# main.net
KiCad netlist of a schematic drawn in EAGLE
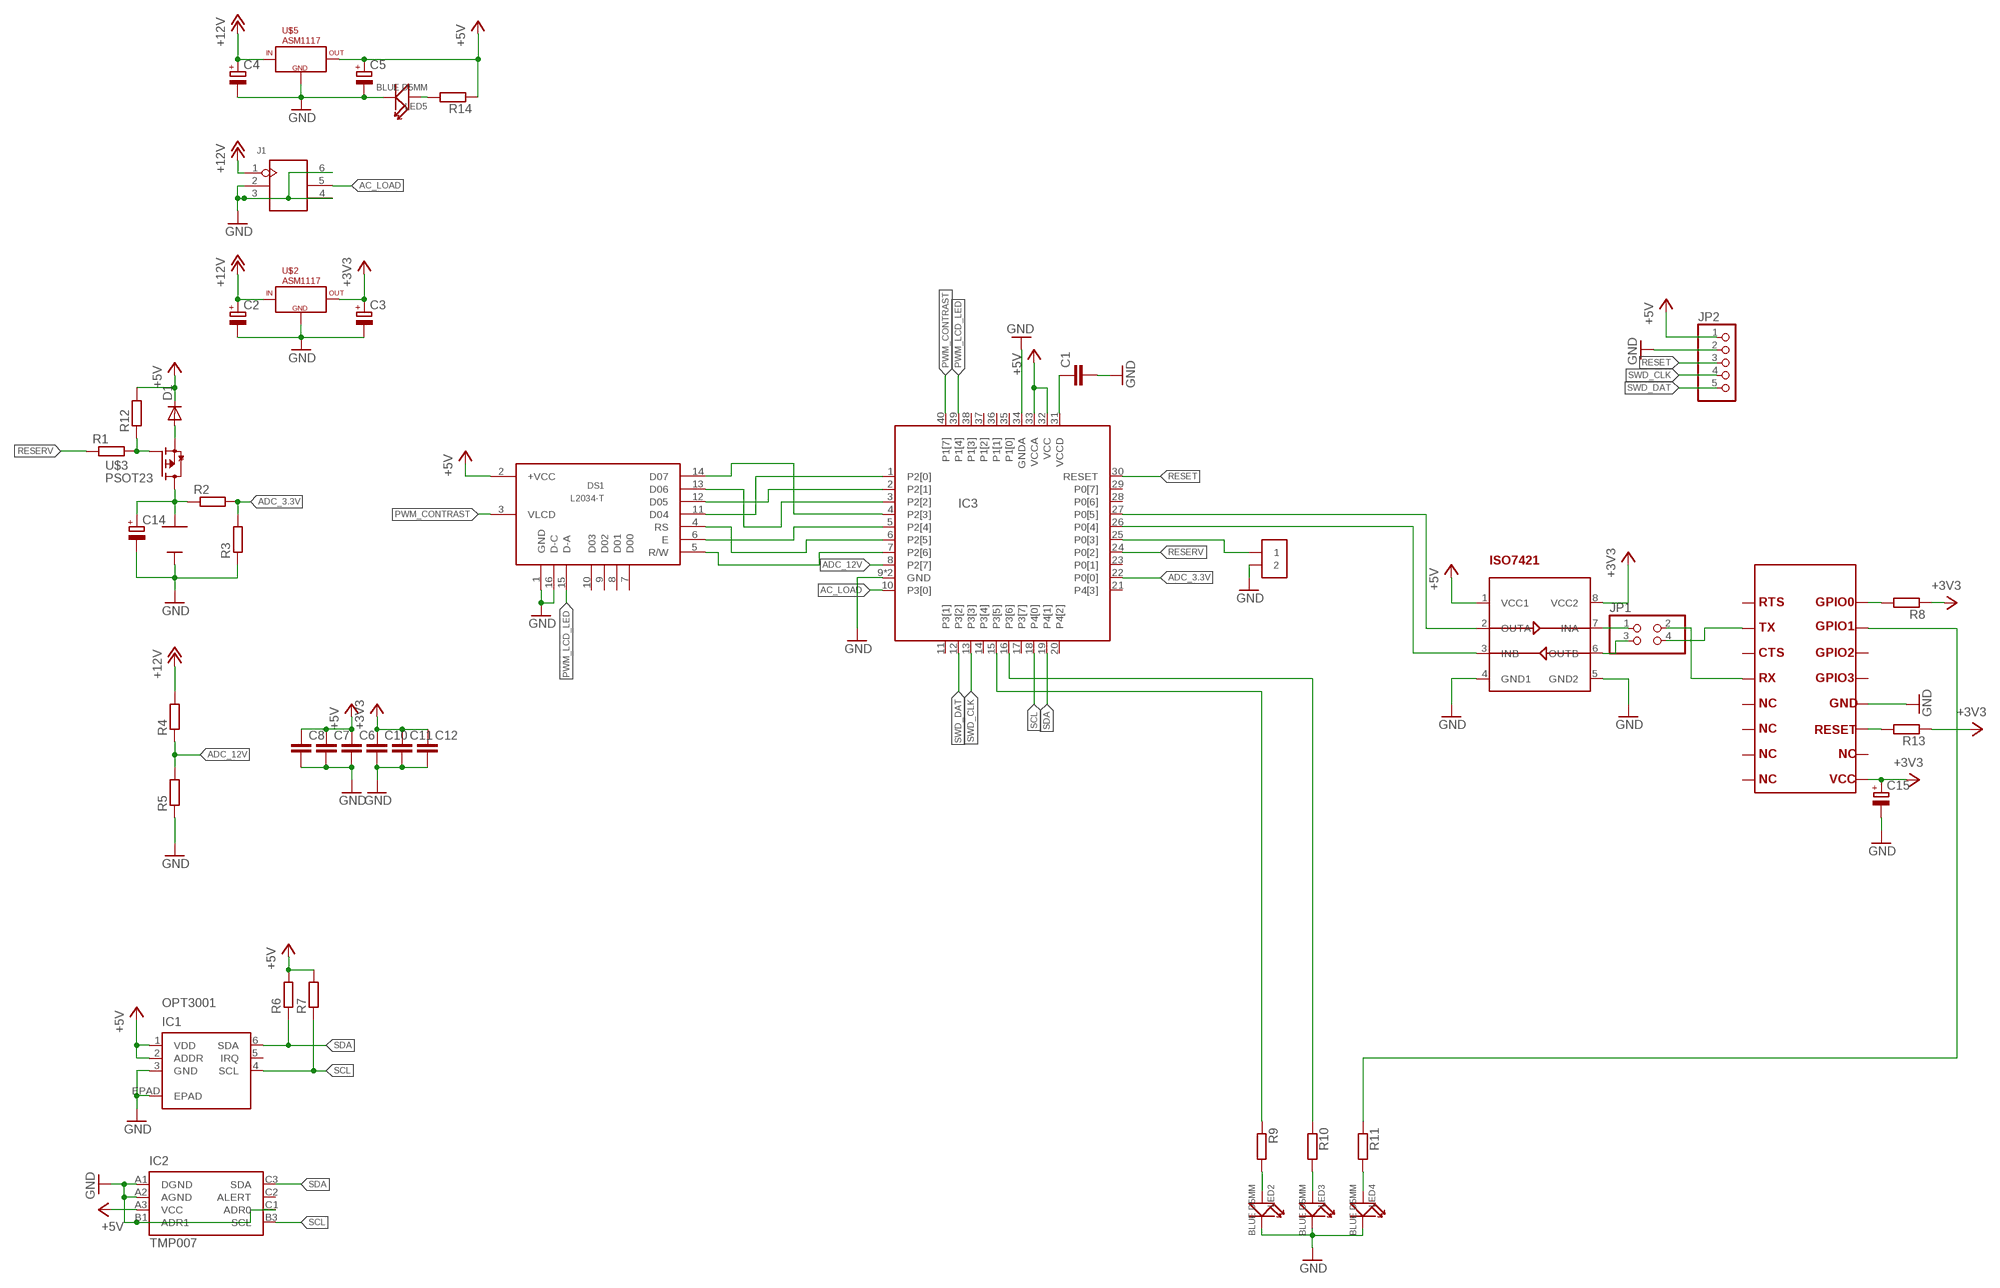
[diagram p0: schematic, sheet 1]

(export (version "E")
  (design (tool "Eeschema 10.0.6"))
  (components
    (comp (ref "BAT1")
      (value "CR2032_DIP")
      (footprint "eagle-import:CR2032_DIP")
      (libsource (lib "eagle-import") (part "CR2032_DIP"))
    )
    (comp (ref "C1")
      (value "C-EUC0805")
      (footprint "eagle-import:C0805")
      (libsource (lib "eagle-import") (part "C-EUC0805"))
    )
    (comp (ref "C2")
      (value "CPOL-EU150CLZ-0810")
      (footprint "eagle-import:150CLZ-0810")
      (libsource (lib "eagle-import") (part "CPOL-EU150CLZ-0810"))
    )
    (comp (ref "C3")
      (value "CPOL-EU150CLZ-0810")
      (footprint "eagle-import:150CLZ-0810")
      (libsource (lib "eagle-import") (part "CPOL-EU150CLZ-0810"))
    )
    (comp (ref "C4")
      (value "CPOL-EU150CLZ-0810")
      (footprint "eagle-import:150CLZ-0810")
      (libsource (lib "eagle-import") (part "CPOL-EU150CLZ-0810"))
    )
    (comp (ref "C5")
      (value "CPOL-EU150CLZ-0810")
      (footprint "eagle-import:150CLZ-0810")
      (libsource (lib "eagle-import") (part "CPOL-EU150CLZ-0810"))
    )
    (comp (ref "C6")
      (value "C-EUC0805")
      (footprint "eagle-import:C0805")
      (libsource (lib "eagle-import") (part "C-EUC0805"))
    )
    (comp (ref "C7")
      (value "C-EUC0805")
      (footprint "eagle-import:C0805")
      (libsource (lib "eagle-import") (part "C-EUC0805"))
    )
    (comp (ref "C8")
      (value "C-EUC0805")
      (footprint "eagle-import:C0805")
      (libsource (lib "eagle-import") (part "C-EUC0805"))
    )
    (comp (ref "C10")
      (value "C-EUC0805")
      (footprint "eagle-import:C0805")
      (libsource (lib "eagle-import") (part "C-EUC0805"))
    )
    (comp (ref "C11")
      (value "C-EUC0805")
      (footprint "eagle-import:C0805")
      (libsource (lib "eagle-import") (part "C-EUC0805"))
    )
    (comp (ref "C12")
      (value "C-EUC0805")
      (footprint "eagle-import:C0805")
      (libsource (lib "eagle-import") (part "C-EUC0805"))
    )
    (comp (ref "C14")
      (value "CPOL-EUSMCD")
      (footprint "eagle-import:SMC_D")
      (libsource (lib "eagle-import") (part "CPOL-EUSMCD"))
    )
    (comp (ref "C15")
      (value "CPOL-EUSMCA")
      (footprint "eagle-import:SMC_A")
      (libsource (lib "eagle-import") (part "CPOL-EUSMCA"))
    )
    (comp (ref "D1")
      (value "DIODE-DO-214AC")
      (footprint "eagle-import:DO-214AC")
      (libsource (lib "eagle-import") (part "DIODE-DO-214AC"))
    )
    (comp (ref "DS1")
      (value "L2034-T")
      (footprint "eagle-import:L2034-T")
      (libsource (lib "eagle-import") (part "L2034-T"))
    )
    (comp (ref "IC1")
      (value "OPT3001")
      (footprint "eagle-import:USON6")
      (libsource (lib "eagle-import") (part "OPT3001"))
    )
    (comp (ref "IC2")
      (value "TMP007")
      (footprint "eagle-import:XBGA8")
      (libsource (lib "eagle-import") (part "TMP007"))
    )
    (comp (ref "IC3")
      (value "CY8C4245-LQI-LONG")
      (footprint "eagle-import:QFN40-LONG")
      (libsource (lib "eagle-import") (part "CY8C4245-LQI-LONG"))
    )
    (comp (ref "J1")
      (value "DIP-BLUE-MALE-HEADER-VERT(2X3P-2.54)")
      (footprint "eagle-import:H2X3-2.54")
      (fields (field (name "MPN") "P125-1203A0BS116A1"))
      (libsource (lib "eagle-import") (part "DIP-BLUE-MALE-HEADER-VERT(2X3P-2.54)"))
    )
    (comp (ref "JP1")
      (value "PINHD-2X2")
      (footprint "eagle-import:2X02")
      (libsource (lib "eagle-import") (part "PINHD-2X2"))
    )
    (comp (ref "JP2")
      (value "PINHD-1X5")
      (footprint "eagle-import:1X05")
      (libsource (lib "eagle-import") (part "PINHD-1X5"))
    )
    (comp (ref "LED2")
      (value "BLUE D5MM")
      (footprint "eagle-import:LED2-2.54-D5.0MM")
      (fields (field (name "MPN") "BH504DC"))
      (libsource (lib "eagle-import") (part "DIP-LED-BLUE-BLUE-5MM(2P-D5MM)"))
    )
    (comp (ref "LED3")
      (value "BLUE D5MM")
      (footprint "eagle-import:LED2-2.54-D5.0MM")
      (fields (field (name "MPN") "BH504DC"))
      (libsource (lib "eagle-import") (part "DIP-LED-BLUE-BLUE-5MM(2P-D5MM)"))
    )
    (comp (ref "LED4")
      (value "BLUE D5MM")
      (footprint "eagle-import:LED2-2.54-D5.0MM")
      (fields (field (name "MPN") "BH504DC"))
      (libsource (lib "eagle-import") (part "DIP-LED-BLUE-BLUE-5MM(2P-D5MM)"))
    )
    (comp (ref "LED5")
      (value "BLUE D5MM")
      (footprint "eagle-import:LED2-2.54-D5.0MM")
      (fields (field (name "MPN") "BH504DC"))
      (libsource (lib "eagle-import") (part "DIP-LED-BLUE-BLUE-5MM(2P-D5MM)"))
    )
    (comp (ref "R1")
      (value "R-EU_M0805")
      (footprint "eagle-import:M0805")
      (libsource (lib "eagle-import") (part "R-EU_M0805"))
    )
    (comp (ref "R2")
      (value "R-EU_M0805")
      (footprint "eagle-import:M0805")
      (libsource (lib "eagle-import") (part "R-EU_M0805"))
    )
    (comp (ref "R3")
      (value "R-EU_M0805")
      (footprint "eagle-import:M0805")
      (libsource (lib "eagle-import") (part "R-EU_M0805"))
    )
    (comp (ref "R4")
      (value "R-EU_M0805")
      (footprint "eagle-import:M0805")
      (libsource (lib "eagle-import") (part "R-EU_M0805"))
    )
    (comp (ref "R5")
      (value "R-EU_M0805")
      (footprint "eagle-import:M0805")
      (libsource (lib "eagle-import") (part "R-EU_M0805"))
    )
    (comp (ref "R6")
      (value "R-EU_M0805")
      (footprint "eagle-import:M0805")
      (libsource (lib "eagle-import") (part "R-EU_M0805"))
    )
    (comp (ref "R7")
      (value "R-EU_M0805")
      (footprint "eagle-import:M0805")
      (libsource (lib "eagle-import") (part "R-EU_M0805"))
    )
    (comp (ref "R8")
      (value "R-EU_M0805")
      (footprint "eagle-import:M0805")
      (libsource (lib "eagle-import") (part "R-EU_M0805"))
    )
    (comp (ref "R9")
      (value "R-EU_M0805")
      (footprint "eagle-import:M0805")
      (libsource (lib "eagle-import") (part "R-EU_M0805"))
    )
    (comp (ref "R10")
      (value "R-EU_M0805")
      (footprint "eagle-import:M0805")
      (libsource (lib "eagle-import") (part "R-EU_M0805"))
    )
    (comp (ref "R11")
      (value "R-EU_M0805")
      (footprint "eagle-import:M0805")
      (libsource (lib "eagle-import") (part "R-EU_M0805"))
    )
    (comp (ref "R12")
      (value "R-EU_M0805")
      (footprint "eagle-import:M0805")
      (libsource (lib "eagle-import") (part "R-EU_M0805"))
    )
    (comp (ref "R13")
      (value "R-EU_M0805")
      (footprint "eagle-import:M0805")
      (libsource (lib "eagle-import") (part "R-EU_M0805"))
    )
    (comp (ref "R14")
      (value "R-EU_M0805")
      (footprint "eagle-import:M0805")
      (libsource (lib "eagle-import") (part "R-EU_M0805"))
    )
    (comp (ref "U$1")
      (value "HM-11")
      (footprint "eagle-import:HM-11")
      (libsource (lib "eagle-import") (part "HM-11"))
    )
    (comp (ref "U$2")
      (value "ASM1117")
      (footprint "eagle-import:SOT223")
      (libsource (lib "eagle-import") (part "ASM1117"))
    )
    (comp (ref "U$3")
      (value "PSOT23")
      (footprint "eagle-import:SOT23")
      (libsource (lib "eagle-import") (part "PSOT23"))
    )
    (comp (ref "U$5")
      (value "ASM1117")
      (footprint "eagle-import:SOT223")
      (libsource (lib "eagle-import") (part "ASM1117"))
    )
    (comp (ref "U$6")
      (value "ISO7421")
      (footprint "eagle-import:SO8")
      (libsource (lib "eagle-import") (part "ISO7421"))
    )
    (comp (ref "U$7")
      (value "1X2")
      (footprint "eagle-import:1X2")
      (libsource (lib "eagle-import") (part "1X2"))
    )
  )
  (nets
    (net (code "1") (name "+3V3") (class "Default")
      (node (ref "C10") (pin "1") (pinfunction "1_1") (pintype "passive"))
      (node (ref "C11") (pin "1") (pinfunction "1_1") (pintype "passive"))
      (node (ref "C12") (pin "1") (pinfunction "1_1") (pintype "passive"))
      (node (ref "C15") (pin "+") (pinfunction "+_+") (pintype "passive"))
      (node (ref "C3") (pin "+") (pinfunction "+_+") (pintype "passive"))
      (node (ref "R13") (pin "1") (pinfunction "1_1") (pintype "passive"))
      (node (ref "R8") (pin "1") (pinfunction "1_1") (pintype "passive"))
      (node (ref "U$1") (pin "9") (pinfunction "P$9_9") (pintype "bidirectional"))
      (node (ref "U$2") (pin "2") (pinfunction "OUT_2") (pintype "power_in"))
      (node (ref "U$2") (pin "4") (pinfunction "OUT_4") (pintype "power_in"))
      (node (ref "U$6") (pin "8") (pinfunction "VCC2_8") (pintype "bidirectional"))
    )
    (net (code "2") (name "+5V") (class "Default")
      (node (ref "C5") (pin "+") (pinfunction "+_+") (pintype "passive"))
      (node (ref "C6") (pin "1") (pinfunction "1_1") (pintype "passive"))
      (node (ref "C7") (pin "1") (pinfunction "1_1") (pintype "passive"))
      (node (ref "C8") (pin "1") (pinfunction "1_1") (pintype "passive"))
      (node (ref "D1") (pin "C") (pinfunction "C_C") (pintype "passive"))
      (node (ref "DS1") (pin "2") (pinfunction "+VCC_2") (pintype "bidirectional"))
      (node (ref "IC1") (pin "1") (pinfunction "VDD_1") (pintype "power_in"))
      (node (ref "IC1") (pin "2") (pinfunction "ADDR_2") (pintype "bidirectional"))
      (node (ref "IC2") (pin "A3") (pinfunction "VCC_A3") (pintype "power_in"))
      (node (ref "IC3") (pin "32") (pinfunction "VCC_32") (pintype "power_in"))
      (node (ref "IC3") (pin "33") (pinfunction "VCCA_33") (pintype "power_in"))
      (node (ref "JP2") (pin "1") (pinfunction "1_1") (pintype "passive"))
      (node (ref "R12") (pin "2") (pinfunction "2_2") (pintype "passive"))
      (node (ref "R14") (pin "1") (pinfunction "1_1") (pintype "passive"))
      (node (ref "R6") (pin "2") (pinfunction "2_2") (pintype "passive"))
      (node (ref "R7") (pin "2") (pinfunction "2_2") (pintype "passive"))
      (node (ref "U$5") (pin "2") (pinfunction "OUT_2") (pintype "power_in"))
      (node (ref "U$5") (pin "4") (pinfunction "OUT_4") (pintype "power_in"))
      (node (ref "U$6") (pin "1") (pinfunction "VCC1_1") (pintype "bidirectional"))
    )
    (net (code "3") (name "+12V") (class "Default")
      (node (ref "C2") (pin "+") (pinfunction "+_+") (pintype "passive"))
      (node (ref "C4") (pin "+") (pinfunction "+_+") (pintype "passive"))
      (node (ref "J1") (pin "1") (pinfunction "1_1") (pintype "bidirectional"))
      (node (ref "R4") (pin "2") (pinfunction "2_2") (pintype "passive"))
      (node (ref "U$2") (pin "3") (pinfunction "IN_3") (pintype "power_in"))
      (node (ref "U$5") (pin "3") (pinfunction "IN_3") (pintype "power_in"))
    )
    (net (code "4") (name "AC_LOAD") (class "Default")
      (node (ref "IC3") (pin "10") (pinfunction "P3[0]_10") (pintype "bidirectional"))
      (node (ref "J1") (pin "5") (pinfunction "5_5") (pintype "bidirectional"))
    )
    (net (code "5") (name "ADC_3.3V") (class "Default")
      (node (ref "IC3") (pin "22") (pinfunction "P0[0]_22") (pintype "bidirectional"))
      (node (ref "R2") (pin "2") (pinfunction "2_2") (pintype "passive"))
      (node (ref "R3") (pin "2") (pinfunction "2_2") (pintype "passive"))
    )
    (net (code "6") (name "ADC_12V") (class "Default")
      (node (ref "IC3") (pin "8") (pinfunction "P2[7]_8") (pintype "bidirectional"))
      (node (ref "R4") (pin "1") (pinfunction "1_1") (pintype "passive"))
      (node (ref "R5") (pin "2") (pinfunction "2_2") (pintype "passive"))
    )
    (net (code "7") (name "GND") (class "Default")
      (node (ref "BAT1") (pin "-") (pinfunction "-_-") (pintype "bidirectional"))
      (node (ref "C1") (pin "2") (pinfunction "2_2") (pintype "passive"))
      (node (ref "C10") (pin "2") (pinfunction "2_2") (pintype "passive"))
      (node (ref "C11") (pin "2") (pinfunction "2_2") (pintype "passive"))
      (node (ref "C12") (pin "2") (pinfunction "2_2") (pintype "passive"))
      (node (ref "C14") (pin "-") (pinfunction "-_-") (pintype "passive"))
      (node (ref "C15") (pin "-") (pinfunction "-_-") (pintype "passive"))
      (node (ref "C2") (pin "-") (pinfunction "-_-") (pintype "passive"))
      (node (ref "C3") (pin "-") (pinfunction "-_-") (pintype "passive"))
      (node (ref "C4") (pin "-") (pinfunction "-_-") (pintype "passive"))
      (node (ref "C5") (pin "-") (pinfunction "-_-") (pintype "passive"))
      (node (ref "C6") (pin "2") (pinfunction "2_2") (pintype "passive"))
      (node (ref "C7") (pin "2") (pinfunction "2_2") (pintype "passive"))
      (node (ref "C8") (pin "2") (pinfunction "2_2") (pintype "passive"))
      (node (ref "DS1") (pin "1") (pinfunction "GND_1") (pintype "bidirectional"))
      (node (ref "DS1") (pin "16") (pinfunction "D-C_16") (pintype "bidirectional"))
      (node (ref "IC1") (pin "3") (pinfunction "GND_3") (pintype "power_in"))
      (node (ref "IC1") (pin "EPAD") (pinfunction "EPAD_EPAD") (pintype "bidirectional"))
      (node (ref "IC2") (pin "A1") (pinfunction "DGND_A1") (pintype "power_in"))
      (node (ref "IC2") (pin "A2") (pinfunction "AGND_A2") (pintype "power_in"))
      (node (ref "IC2") (pin "B1") (pinfunction "ADR1_B1") (pintype "bidirectional"))
      (node (ref "IC2") (pin "C1") (pinfunction "ADR0_C1") (pintype "bidirectional"))
      (node (ref "IC3") (pin "34") (pinfunction "GNDA_34") (pintype "power_in"))
      (node (ref "IC3") (pin "41") (pinfunction "GND_41") (pintype "power_in"))
      (node (ref "IC3") (pin "9") (pinfunction "GND_9") (pintype "power_in"))
      (node (ref "J1") (pin "2") (pinfunction "2_2") (pintype "bidirectional"))
      (node (ref "J1") (pin "3") (pinfunction "3_3") (pintype "bidirectional"))
      (node (ref "J1") (pin "4") (pinfunction "4_4") (pintype "bidirectional"))
      (node (ref "J1") (pin "6") (pinfunction "6_6") (pintype "bidirectional"))
      (node (ref "JP2") (pin "2") (pinfunction "2_2") (pintype "passive"))
      (node (ref "LED2") (pin "-") (pinfunction "-_-") (pintype "passive"))
      (node (ref "LED3") (pin "-") (pinfunction "-_-") (pintype "passive"))
      (node (ref "LED4") (pin "-") (pinfunction "-_-") (pintype "passive"))
      (node (ref "LED5") (pin "-") (pinfunction "-_-") (pintype "passive"))
      (node (ref "R3") (pin "1") (pinfunction "1_1") (pintype "passive"))
      (node (ref "R5") (pin "1") (pinfunction "1_1") (pintype "passive"))
      (node (ref "U$1") (pin "12") (pinfunction "P$12_12") (pintype "bidirectional"))
      (node (ref "U$2") (pin "1") (pinfunction "GND_1") (pintype "power_in"))
      (node (ref "U$5") (pin "1") (pinfunction "GND_1") (pintype "power_in"))
      (node (ref "U$6") (pin "4") (pinfunction "GND1_4") (pintype "bidirectional"))
      (node (ref "U$6") (pin "5") (pinfunction "GND2_5") (pintype "bidirectional"))
      (node (ref "U$7") (pin "2") (pinfunction "2_2") (pintype "bidirectional"))
    )
    (net (code "8") (name "Net-(BAT1-Pad+)") (class "Default")
      (node (ref "BAT1") (pin "+") (pinfunction "+_+") (pintype "bidirectional"))
      (node (ref "C14") (pin "+") (pinfunction "+_+") (pintype "passive"))
      (node (ref "R2") (pin "1") (pinfunction "1_1") (pintype "passive"))
      (node (ref "U$3") (pin "S") (pinfunction "S_S") (pintype "passive"))
    )
    (net (code "9") (name "Net-(D1-PadA)") (class "Default")
      (node (ref "D1") (pin "A") (pinfunction "A_A") (pintype "passive"))
      (node (ref "U$3") (pin "D") (pinfunction "D_D") (pintype "passive"))
    )
    (net (code "10") (name "Net-(DS1-D04)") (class "Default")
      (node (ref "DS1") (pin "11") (pinfunction "D04_11") (pintype "bidirectional"))
      (node (ref "IC3") (pin "1") (pinfunction "P2[0]_1") (pintype "bidirectional"))
    )
    (net (code "11") (name "Net-(DS1-D05)") (class "Default")
      (node (ref "DS1") (pin "12") (pinfunction "D05_12") (pintype "bidirectional"))
      (node (ref "IC3") (pin "2") (pinfunction "P2[1]_2") (pintype "bidirectional"))
    )
    (net (code "12") (name "Net-(DS1-D06)") (class "Default")
      (node (ref "DS1") (pin "13") (pinfunction "D06_13") (pintype "bidirectional"))
      (node (ref "IC3") (pin "3") (pinfunction "P2[2]_3") (pintype "bidirectional"))
    )
    (net (code "13") (name "Net-(DS1-D07)") (class "Default")
      (node (ref "DS1") (pin "14") (pinfunction "D07_14") (pintype "bidirectional"))
      (node (ref "IC3") (pin "4") (pinfunction "P2[3]_4") (pintype "bidirectional"))
    )
    (net (code "14") (name "Net-(DS1-E)") (class "Default")
      (node (ref "DS1") (pin "6") (pinfunction "E_6") (pintype "bidirectional"))
      (node (ref "IC3") (pin "5") (pinfunction "P2[4]_5") (pintype "bidirectional"))
    )
    (net (code "15") (name "Net-(DS1-RS)") (class "Default")
      (node (ref "DS1") (pin "4") (pinfunction "RS_4") (pintype "bidirectional"))
      (node (ref "IC3") (pin "6") (pinfunction "P2[5]_6") (pintype "bidirectional"))
    )
    (net (code "16") (name "Net-(DS1-R{slash}W)") (class "Default")
      (node (ref "DS1") (pin "5") (pinfunction "R/W_5") (pintype "bidirectional"))
      (node (ref "IC3") (pin "7") (pinfunction "P2[6]_7") (pintype "bidirectional"))
    )
    (net (code "17") (name "Net-(IC3-P0[3])") (class "Default")
      (node (ref "IC3") (pin "25") (pinfunction "P0[3]_25") (pintype "bidirectional"))
      (node (ref "U$7") (pin "1") (pinfunction "1_1") (pintype "bidirectional"))
    )
    (net (code "18") (name "Net-(IC3-P0[4])") (class "Default")
      (node (ref "IC3") (pin "26") (pinfunction "P0[4]_26") (pintype "bidirectional"))
      (node (ref "U$6") (pin "3") (pinfunction "INB_3") (pintype "bidirectional"))
    )
    (net (code "19") (name "Net-(IC3-P0[5])") (class "Default")
      (node (ref "IC3") (pin "27") (pinfunction "P0[5]_27") (pintype "bidirectional"))
      (node (ref "U$6") (pin "2") (pinfunction "OUTA_2") (pintype "bidirectional"))
    )
    (net (code "20") (name "Net-(IC3-P3[5])") (class "Default")
      (node (ref "IC3") (pin "15") (pinfunction "P3[5]_15") (pintype "bidirectional"))
      (node (ref "R9") (pin "1") (pinfunction "1_1") (pintype "passive"))
    )
    (net (code "21") (name "Net-(IC3-P3[6])") (class "Default")
      (node (ref "IC3") (pin "16") (pinfunction "P3[6]_16") (pintype "bidirectional"))
      (node (ref "R10") (pin "1") (pinfunction "1_1") (pintype "passive"))
    )
    (net (code "22") (name "Net-(IC3-VCCD)") (class "Default")
      (node (ref "C1") (pin "1") (pinfunction "1_1") (pintype "passive"))
      (node (ref "IC3") (pin "31") (pinfunction "VCCD_31") (pintype "power_in"))
    )
    (net (code "23") (name "Net-(LED2-Pad+)") (class "Default")
      (node (ref "LED2") (pin "+") (pinfunction "+_+") (pintype "passive"))
      (node (ref "R9") (pin "2") (pinfunction "2_2") (pintype "passive"))
    )
    (net (code "24") (name "Net-(LED3-Pad+)") (class "Default")
      (node (ref "LED3") (pin "+") (pinfunction "+_+") (pintype "passive"))
      (node (ref "R10") (pin "2") (pinfunction "2_2") (pintype "passive"))
    )
    (net (code "25") (name "Net-(LED4-Pad+)") (class "Default")
      (node (ref "LED4") (pin "+") (pinfunction "+_+") (pintype "passive"))
      (node (ref "R11") (pin "2") (pinfunction "2_2") (pintype "passive"))
    )
    (net (code "26") (name "Net-(LED5-Pad+)") (class "Default")
      (node (ref "LED5") (pin "+") (pinfunction "+_+") (pintype "passive"))
      (node (ref "R14") (pin "2") (pinfunction "2_2") (pintype "passive"))
    )
    (net (code "27") (name "Net-(R1-Pad2)") (class "Default")
      (node (ref "R1") (pin "2") (pinfunction "2_2") (pintype "passive"))
      (node (ref "R12") (pin "1") (pinfunction "1_1") (pintype "passive"))
      (node (ref "U$3") (pin "G") (pinfunction "G_G") (pintype "passive"))
    )
    (net (code "28") (name "Net-(U$1-P$2)") (class "Default")
      (node (ref "JP1") (pin "4") (pinfunction "4_4") (pintype "passive"))
      (node (ref "U$1") (pin "2") (pinfunction "P$2_2") (pintype "bidirectional"))
    )
    (net (code "29") (name "Net-(U$1-P$4)") (class "Default")
      (node (ref "JP1") (pin "2") (pinfunction "2_2") (pintype "passive"))
      (node (ref "U$1") (pin "4") (pinfunction "P$4_4") (pintype "bidirectional"))
    )
    (net (code "30") (name "Net-(U$1-P$11)") (class "Default")
      (node (ref "R13") (pin "2") (pinfunction "2_2") (pintype "passive"))
      (node (ref "U$1") (pin "11") (pinfunction "P$11_11") (pintype "bidirectional"))
    )
    (net (code "31") (name "Net-(U$1-P$15)") (class "Default")
      (node (ref "R11") (pin "1") (pinfunction "1_1") (pintype "passive"))
      (node (ref "U$1") (pin "15") (pinfunction "P$15_15") (pintype "bidirectional"))
    )
    (net (code "32") (name "Net-(U$1-P$16)") (class "Default")
      (node (ref "R8") (pin "2") (pinfunction "2_2") (pintype "passive"))
      (node (ref "U$1") (pin "16") (pinfunction "P$16_16") (pintype "bidirectional"))
    )
    (net (code "33") (name "Net-(U$6-INA)") (class "Default")
      (node (ref "JP1") (pin "1") (pinfunction "1_1") (pintype "passive"))
      (node (ref "U$6") (pin "7") (pinfunction "INA_7") (pintype "bidirectional"))
    )
    (net (code "34") (name "Net-(U$6-OUTB)") (class "Default")
      (node (ref "JP1") (pin "3") (pinfunction "3_3") (pintype "passive"))
      (node (ref "U$6") (pin "6") (pinfunction "OUTB_6") (pintype "bidirectional"))
    )
    (net (code "35") (name "PWM_CONTRAST") (class "Default")
      (node (ref "DS1") (pin "3") (pinfunction "VLCD_3") (pintype "bidirectional"))
      (node (ref "IC3") (pin "40") (pinfunction "P1[7]_40") (pintype "bidirectional"))
    )
    (net (code "36") (name "PWM_LCD_LED") (class "Default")
      (node (ref "DS1") (pin "15") (pinfunction "D-A_15") (pintype "bidirectional"))
      (node (ref "IC3") (pin "39") (pinfunction "P1[4]_39") (pintype "bidirectional"))
    )
    (net (code "37") (name "RESERV") (class "Default")
      (node (ref "IC3") (pin "24") (pinfunction "P0[2]_24") (pintype "bidirectional"))
      (node (ref "R1") (pin "1") (pinfunction "1_1") (pintype "passive"))
    )
    (net (code "38") (name "RESET") (class "Default")
      (node (ref "IC3") (pin "30") (pinfunction "RESET_30") (pintype "input"))
      (node (ref "JP2") (pin "3") (pinfunction "3_3") (pintype "passive"))
    )
    (net (code "39") (name "SCL") (class "Default")
      (node (ref "IC1") (pin "4") (pinfunction "SCL_4") (pintype "bidirectional"))
      (node (ref "IC2") (pin "B3") (pinfunction "SCL_B3") (pintype "bidirectional"))
      (node (ref "IC3") (pin "18") (pinfunction "P4[0]_18") (pintype "bidirectional"))
      (node (ref "R7") (pin "1") (pinfunction "1_1") (pintype "passive"))
    )
    (net (code "40") (name "SDA") (class "Default")
      (node (ref "IC1") (pin "6") (pinfunction "SDA_6") (pintype "bidirectional"))
      (node (ref "IC2") (pin "C3") (pinfunction "SDA_C3") (pintype "bidirectional"))
      (node (ref "IC3") (pin "19") (pinfunction "P4[1]_19") (pintype "bidirectional"))
      (node (ref "R6") (pin "1") (pinfunction "1_1") (pintype "passive"))
    )
    (net (code "41") (name "SWD_CLK") (class "Default")
      (node (ref "IC3") (pin "13") (pinfunction "P3[3]_13") (pintype "bidirectional"))
      (node (ref "JP2") (pin "4") (pinfunction "4_4") (pintype "passive"))
    )
    (net (code "42") (name "SWD_DAT") (class "Default")
      (node (ref "IC3") (pin "12") (pinfunction "P3[2]_12") (pintype "bidirectional"))
      (node (ref "JP2") (pin "5") (pinfunction "5_5") (pintype "passive"))
    )
    (net (code "43") (name "unconnected-(DS1-D00-Pad7)") (class "Default")
      (node (ref "DS1") (pin "7") (pinfunction "D00_7") (pintype "bidirectional"))
    )
    (net (code "44") (name "unconnected-(DS1-D01-Pad8)") (class "Default")
      (node (ref "DS1") (pin "8") (pinfunction "D01_8") (pintype "bidirectional"))
    )
    (net (code "45") (name "unconnected-(DS1-D02-Pad9)") (class "Default")
      (node (ref "DS1") (pin "9") (pinfunction "D02_9") (pintype "bidirectional"))
    )
    (net (code "46") (name "unconnected-(DS1-D03-Pad10)") (class "Default")
      (node (ref "DS1") (pin "10") (pinfunction "D03_10") (pintype "bidirectional"))
    )
    (net (code "47") (name "unconnected-(IC1-IRQ-Pad5)") (class "Default")
      (node (ref "IC1") (pin "5") (pinfunction "IRQ_5") (pintype "bidirectional"))
    )
    (net (code "48") (name "unconnected-(IC2-ALERT-PadC2)") (class "Default")
      (node (ref "IC2") (pin "C2") (pinfunction "ALERT_C2") (pintype "bidirectional"))
    )
    (net (code "49") (name "unconnected-(IC3-P0[1]-Pad23)") (class "Default")
      (node (ref "IC3") (pin "23") (pinfunction "P0[1]_23") (pintype "bidirectional"))
    )
    (net (code "50") (name "unconnected-(IC3-P0[6]-Pad28)") (class "Default")
      (node (ref "IC3") (pin "28") (pinfunction "P0[6]_28") (pintype "bidirectional"))
    )
    (net (code "51") (name "unconnected-(IC3-P0[7]-Pad29)") (class "Default")
      (node (ref "IC3") (pin "29") (pinfunction "P0[7]_29") (pintype "bidirectional"))
    )
    (net (code "52") (name "unconnected-(IC3-P1[0]-Pad35)") (class "Default")
      (node (ref "IC3") (pin "35") (pinfunction "P1[0]_35") (pintype "bidirectional"))
    )
    (net (code "53") (name "unconnected-(IC3-P1[1]-Pad36)") (class "Default")
      (node (ref "IC3") (pin "36") (pinfunction "P1[1]_36") (pintype "bidirectional"))
    )
    (net (code "54") (name "unconnected-(IC3-P1[2]-Pad37)") (class "Default")
      (node (ref "IC3") (pin "37") (pinfunction "P1[2]_37") (pintype "bidirectional"))
    )
    (net (code "55") (name "unconnected-(IC3-P1[3]-Pad38)") (class "Default")
      (node (ref "IC3") (pin "38") (pinfunction "P1[3]_38") (pintype "bidirectional"))
    )
    (net (code "56") (name "unconnected-(IC3-P3[1]-Pad11)") (class "Default")
      (node (ref "IC3") (pin "11") (pinfunction "P3[1]_11") (pintype "bidirectional"))
    )
    (net (code "57") (name "unconnected-(IC3-P3[4]-Pad14)") (class "Default")
      (node (ref "IC3") (pin "14") (pinfunction "P3[4]_14") (pintype "bidirectional"))
    )
    (net (code "58") (name "unconnected-(IC3-P3[7]-Pad17)") (class "Default")
      (node (ref "IC3") (pin "17") (pinfunction "P3[7]_17") (pintype "bidirectional"))
    )
    (net (code "59") (name "unconnected-(IC3-P4[2]-Pad20)") (class "Default")
      (node (ref "IC3") (pin "20") (pinfunction "P4[2]_20") (pintype "bidirectional"))
    )
    (net (code "60") (name "unconnected-(IC3-P4[3]-Pad21)") (class "Default")
      (node (ref "IC3") (pin "21") (pinfunction "P4[3]_21") (pintype "bidirectional"))
    )
    (net (code "61") (name "unconnected-(U$1-P$1-Pad1)") (class "Default")
      (node (ref "U$1") (pin "1") (pinfunction "P$1_1") (pintype "bidirectional"))
    )
    (net (code "62") (name "unconnected-(U$1-P$3-Pad3)") (class "Default")
      (node (ref "U$1") (pin "3") (pinfunction "P$3_3") (pintype "bidirectional"))
    )
    (net (code "63") (name "unconnected-(U$1-P$5-Pad5)") (class "Default")
      (node (ref "U$1") (pin "5") (pinfunction "P$5_5") (pintype "bidirectional"))
    )
    (net (code "64") (name "unconnected-(U$1-P$6-Pad6)") (class "Default")
      (node (ref "U$1") (pin "6") (pinfunction "P$6_6") (pintype "bidirectional"))
    )
    (net (code "65") (name "unconnected-(U$1-P$7-Pad7)") (class "Default")
      (node (ref "U$1") (pin "7") (pinfunction "P$7_7") (pintype "bidirectional"))
    )
    (net (code "66") (name "unconnected-(U$1-P$8-Pad8)") (class "Default")
      (node (ref "U$1") (pin "8") (pinfunction "P$8_8") (pintype "bidirectional"))
    )
    (net (code "67") (name "unconnected-(U$1-P$10-Pad10)") (class "Default")
      (node (ref "U$1") (pin "10") (pinfunction "P$10_10") (pintype "bidirectional"))
    )
    (net (code "68") (name "unconnected-(U$1-P$13-Pad13)") (class "Default")
      (node (ref "U$1") (pin "13") (pinfunction "P$13_13") (pintype "bidirectional"))
    )
    (net (code "69") (name "unconnected-(U$1-P$14-Pad14)") (class "Default")
      (node (ref "U$1") (pin "14") (pinfunction "P$14_14") (pintype "bidirectional"))
    )
  )
)
